# Sockets.net
KiCad netlist of a schematic drawn in Altium Designer
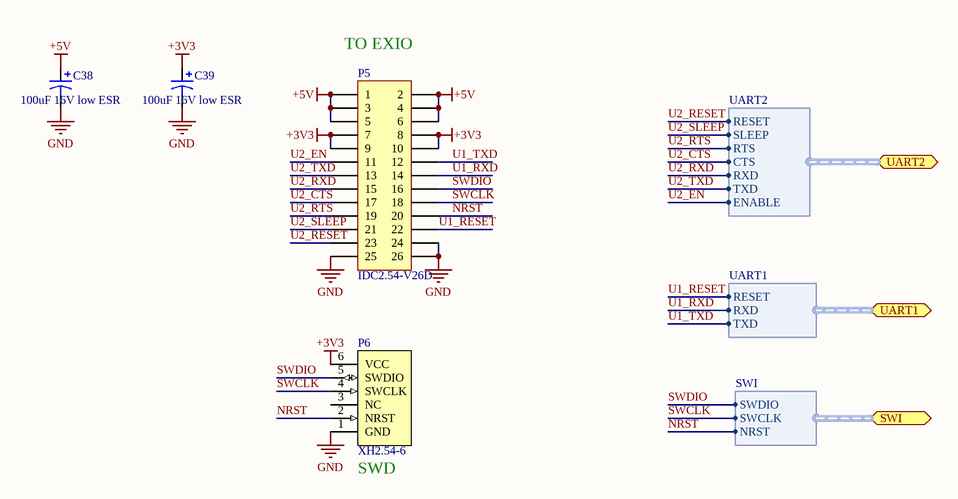
[diagram p0: Sockets.SchDoc]

(export (version "E")
  (design (tool "Eeschema 10.0.6"))
  (components
    (comp (ref "C38")
      (value "100uF 16V low ESR")
      (footprint "Capacitor Polar Radial Cylinder:CAPPR2-5x11")
      (description "Polarized Capacitor (Radial)")
      (libsource (lib "Miscellaneous Devices") (part "Cap Pol1"))
    )
    (comp (ref "C39")
      (value "100uF 16V low ESR")
      (footprint "Capacitor Polar Radial Cylinder:CAPPR2-5x11")
      (description "Polarized Capacitor (Radial)")
      (libsource (lib "Miscellaneous Devices") (part "Cap Pol1"))
    )
    (comp (ref "P5")
      (value "IDC2.54-V26D")
      (footprint "Con IDC:IDC2.54-V26D")
      (description "IDC2.54-13x2 Header")
      (fields (field (name "PUBLISHER") "Altium Limited"))
      (libsource (lib "Miscellaneous Connectors") (part "Header 13X2"))
    )
    (comp (ref "P6")
      (value "XH2.54-6")
      (footprint "UserPcbLib:REAL_SIP6_2.54")
      (description "SW debug connector")
      (libsource (lib "UserSchlib") (part "SWD-Connector"))
    )
  )
  (nets
    (net (code "4") (name "+3V3") (class "Default")
      (node (ref "C39") (pin "1") (pinfunction "1_1") (pintype "passive"))
      (node (ref "P5") (pin "10") (pinfunction "10_10") (pintype "passive"))
      (node (ref "P5") (pin "7") (pinfunction "7_7") (pintype "passive"))
      (node (ref "P5") (pin "8") (pinfunction "8_8") (pintype "passive"))
      (node (ref "P5") (pin "9") (pinfunction "9_9") (pintype "passive"))
      (node (ref "P6") (pin "6") (pinfunction "VCC_6") (pintype "power_in"))
    )
    (net (code "5") (name "+5V") (class "Default")
      (node (ref "C38") (pin "1") (pinfunction "1_1") (pintype "passive"))
      (node (ref "P5") (pin "1") (pinfunction "1_1") (pintype "passive"))
      (node (ref "P5") (pin "2") (pinfunction "2_2") (pintype "passive"))
      (node (ref "P5") (pin "3") (pinfunction "3_3") (pintype "passive"))
      (node (ref "P5") (pin "4") (pinfunction "4_4") (pintype "passive"))
      (node (ref "P5") (pin "5") (pinfunction "5_5") (pintype "passive"))
      (node (ref "P5") (pin "6") (pinfunction "6_6") (pintype "passive"))
    )
    (net (code "6") (name "/NRST") (class "Default")
      (node (ref "P5") (pin "20") (pinfunction "20_20") (pintype "passive"))
      (node (ref "P6") (pin "2") (pinfunction "NRST_2") (pintype "input"))
    )
    (net (code "7") (name "/SWCLK") (class "Default")
      (node (ref "P5") (pin "18") (pinfunction "18_18") (pintype "passive"))
      (node (ref "P6") (pin "4") (pinfunction "SWCLK_4") (pintype "input"))
    )
    (net (code "8") (name "/SWDIO") (class "Default")
      (node (ref "P5") (pin "16") (pinfunction "16_16") (pintype "passive"))
      (node (ref "P6") (pin "5") (pinfunction "SWDIO_5") (pintype "bidirectional"))
    )
    (net (code "9") (name "/U1_RESET") (class "Default")
      (node (ref "P5") (pin "22") (pinfunction "22_22") (pintype "passive"))
    )
    (net (code "10") (name "/U1_RXD") (class "Default")
      (node (ref "P5") (pin "14") (pinfunction "14_14") (pintype "passive"))
    )
    (net (code "11") (name "/U1_TXD") (class "Default")
      (node (ref "P5") (pin "12") (pinfunction "12_12") (pintype "passive"))
    )
    (net (code "12") (name "/U2_CTS") (class "Default")
      (node (ref "P5") (pin "17") (pinfunction "17_17") (pintype "passive"))
    )
    (net (code "13") (name "/U2_EN") (class "Default")
      (node (ref "P5") (pin "11") (pinfunction "11_11") (pintype "passive"))
    )
    (net (code "14") (name "/U2_RESET") (class "Default")
      (node (ref "P5") (pin "23") (pinfunction "23_23") (pintype "passive"))
    )
    (net (code "15") (name "/U2_RTS") (class "Default")
      (node (ref "P5") (pin "19") (pinfunction "19_19") (pintype "passive"))
    )
    (net (code "16") (name "/U2_RXD") (class "Default")
      (node (ref "P5") (pin "15") (pinfunction "15_15") (pintype "passive"))
    )
    (net (code "17") (name "/U2_SLEEP") (class "Default")
      (node (ref "P5") (pin "21") (pinfunction "21_21") (pintype "passive"))
    )
    (net (code "18") (name "/U2_TXD") (class "Default")
      (node (ref "P5") (pin "13") (pinfunction "13_13") (pintype "passive"))
    )
    (net (code "22") (name "GND") (class "Default")
      (node (ref "C38") (pin "2") (pinfunction "2_2") (pintype "passive"))
      (node (ref "C39") (pin "2") (pinfunction "2_2") (pintype "passive"))
      (node (ref "P5") (pin "24") (pinfunction "24_24") (pintype "passive"))
      (node (ref "P5") (pin "25") (pinfunction "25_25") (pintype "passive"))
      (node (ref "P5") (pin "26") (pinfunction "26_26") (pintype "passive"))
      (node (ref "P6") (pin "1") (pinfunction "GND_1") (pintype "power_in"))
    )
    (net (code "23") (name "unconnected-(P6-NC-Pad3)") (class "Default")
      (node (ref "P6") (pin "3") (pinfunction "NC_3") (pintype "power_in"))
    )
  )
)
